# PROC010C_XDS110_Interface_1A.net
KiCad netlist of a schematic drawn in Altium Designer
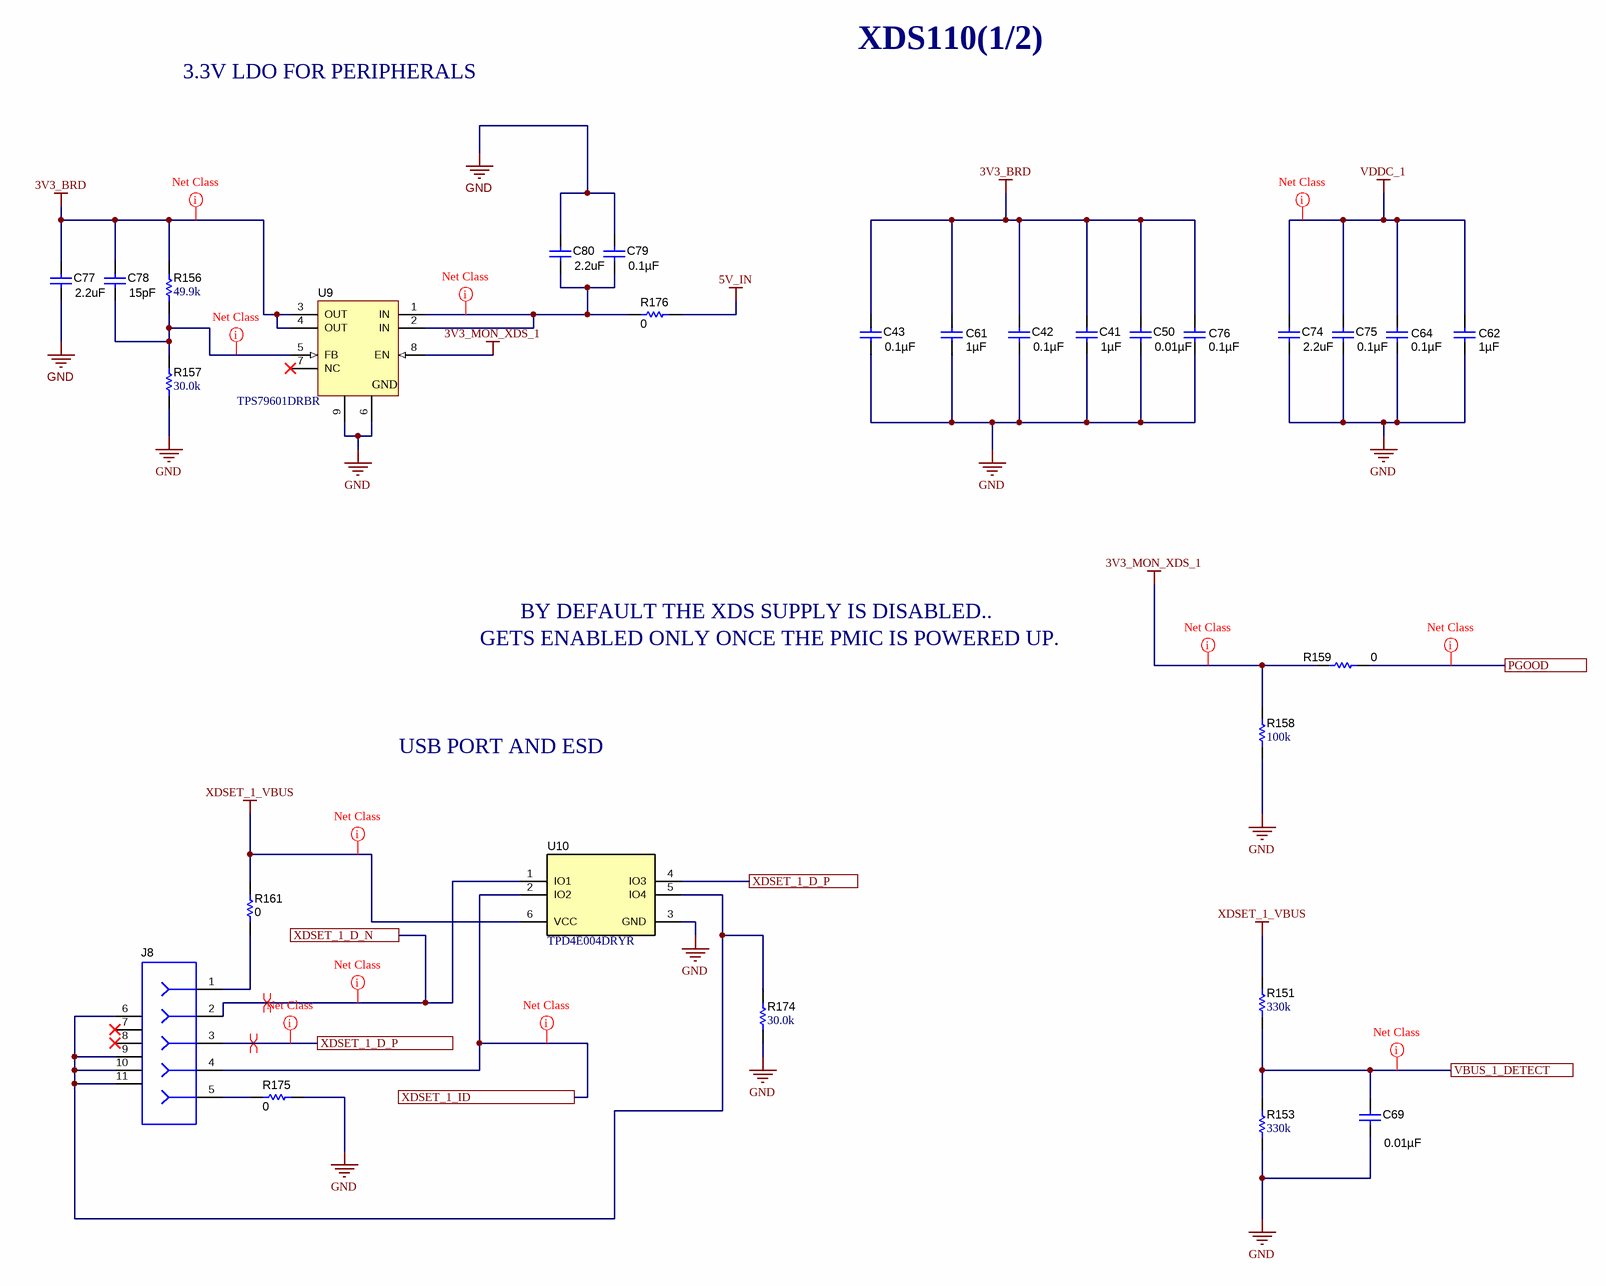
[diagram p0: PROC010C_XDS110 Interface_1A.SchDoc]

(export (version "E")
  (design (tool "Eeschema 10.0.6"))
  (components
    (comp (ref "C41")
      (value "C1005X7S0J105M050BC")
      (footprint "0402L")
      (description "CAP, CERM, 1 µF, 6.3 V,+/- 20%, X7S, 0402")
      (fields (field (name "MANUFACTURER") "TDK") (field (name "VALUEDISPLAYED") "1µF"))
      (libsource (lib "Altium Vault - TI") (part "Capacitor"))
    )
    (comp (ref "C42")
      (value "C0402C104K8RACTU")
      (footprint "0402L")
      (description "CAP, CERM, 0.1 µF, 10 V,+/- 10%, X7R, 0402")
      (fields (field (name "MANUFACTURER") "Kemet") (field (name "VALUEDISPLAYED") "0.1µF"))
      (libsource (lib "Altium Vault - TI") (part "Capacitor"))
    )
    (comp (ref "C43")
      (value "C0402C104K8RACTU")
      (footprint "0402L")
      (description "CAP, CERM, 0.1 µF, 10 V,+/- 10%, X7R, 0402")
      (fields (field (name "MANUFACTURER") "Kemet") (field (name "VALUEDISPLAYED") "0.1µF"))
      (libsource (lib "Altium Vault - TI") (part "Capacitor"))
    )
    (comp (ref "C50")
      (value "C1005X7R1E103K050BB")
      (footprint "0402L")
      (description "CAP, CERM, 0.01 µF, 25 V,+/- 10%, X7R, 0402")
      (fields (field (name "MANUFACTURER") "TDK") (field (name "VALUEDISPLAYED") "0.01µF"))
      (libsource (lib "Altium Vault - TI") (part "Capacitor"))
    )
    (comp (ref "C61")
      (value "C1005X7S0J105M050BC")
      (footprint "0402L")
      (description "CAP, CERM, 1 µF, 6.3 V,+/- 20%, X7S, 0402")
      (fields (field (name "MANUFACTURER") "TDK") (field (name "VALUEDISPLAYED") "1µF"))
      (libsource (lib "Altium Vault - TI") (part "Capacitor"))
    )
    (comp (ref "C62")
      (value "C1005X7S0J105M050BC")
      (footprint "0402L")
      (description "CAP, CERM, 1 µF, 6.3 V,+/- 20%, X7S, 0402")
      (fields (field (name "MANUFACTURER") "TDK") (field (name "VALUEDISPLAYED") "1µF"))
      (libsource (lib "Altium Vault - TI") (part "Capacitor"))
    )
    (comp (ref "C64")
      (value "C0402C104K8RACTU")
      (footprint "0402L")
      (description "CAP, CERM, 0.1 µF, 10 V,+/- 10%, X7R, 0402")
      (fields (field (name "MANUFACTURER") "Kemet") (field (name "VALUEDISPLAYED") "0.1µF"))
      (libsource (lib "Altium Vault - TI") (part "Capacitor"))
    )
    (comp (ref "C69")
      (value "C0402C103K4RACTU")
      (footprint "0402L")
      (description "CAP, CERM, 0.01 µF, 16 V,+/- 10%, X7R, 0402")
      (fields (field (name "MANUFACTURER") "Kemet") (field (name "VALUEDISPLAYED") "0.01µF"))
      (libsource (lib "Altium Vault - TI") (part "Capacitor"))
    )
    (comp (ref "C74")
      (value "C1005X7S1A225K050BC")
      (footprint "0402_065L")
      (description "CAP, CERM, 2.2 uF, 10 V, +/- 10%, X7S, 0402")
      (fields
        (field (name "MANUFACTURER") "TDK")
        (field (name "VALUEDISPLAYED") "2.2uF")
        (field (name "PUBLISHER") "Texas Instruments")
      )
      (libsource (lib "Altium Vault - TI") (part "CMP-0006302-2"))
    )
    (comp (ref "C75")
      (value "C0402C104K8RACTU")
      (footprint "0402L")
      (description "CAP, CERM, 0.1 µF, 10 V,+/- 10%, X7R, 0402")
      (fields (field (name "MANUFACTURER") "Kemet") (field (name "VALUEDISPLAYED") "0.1µF"))
      (libsource (lib "Altium Vault - TI") (part "Capacitor"))
    )
    (comp (ref "C76")
      (value "C0402C104K8RACTU")
      (footprint "0402L")
      (description "CAP, CERM, 0.1 µF, 10 V,+/- 10%, X7R, 0402")
      (fields (field (name "MANUFACTURER") "Kemet") (field (name "VALUEDISPLAYED") "0.1µF"))
      (libsource (lib "Altium Vault - TI") (part "Capacitor"))
    )
    (comp (ref "C77")
      (value "C1005X7S1A225K050BC")
      (footprint "0402_065L")
      (description "CAP, CERM, 2.2 uF, 10 V, +/- 10%, X7S, 0402")
      (fields
        (field (name "MANUFACTURER") "TDK")
        (field (name "VALUEDISPLAYED") "2.2uF")
        (field (name "PUBLISHER") "Texas Instruments")
      )
      (libsource (lib "Altium Vault - TI") (part "CMP-0006302-2"))
    )
    (comp (ref "C78")
      (value "04025A150FAT2A")
      (footprint "0402L")
      (description "CAP, CERM, 15 pF, 50 V,+/- 1%, C0G/NP0, 0402")
      (fields (field (name "MANUFACTURER") "AVX") (field (name "VALUEDISPLAYED") "15pF"))
      (libsource (lib "Altium Vault - TI") (part "Capacitor"))
    )
    (comp (ref "C79")
      (value "C0402C104K8RACTU")
      (footprint "0402L")
      (description "CAP, CERM, 0.1 µF, 10 V,+/- 10%, X7R, 0402")
      (fields (field (name "MANUFACTURER") "Kemet") (field (name "VALUEDISPLAYED") "0.1µF"))
      (libsource (lib "Altium Vault - TI") (part "Capacitor"))
    )
    (comp (ref "C80")
      (value "C1005X7S1A225K050BC")
      (footprint "0402_065L")
      (description "CAP, CERM, 2.2 uF, 10 V, +/- 10%, X7S, 0402")
      (fields
        (field (name "MANUFACTURER") "TDK")
        (field (name "VALUEDISPLAYED") "2.2uF")
        (field (name "PUBLISHER") "Texas Instruments")
      )
      (libsource (lib "Altium Vault - TI") (part "CMP-0006302-2"))
    )
    (comp (ref "J8")
      (value "105017-0001")
      (footprint "CONN_105017-0001")
      (description "Connector, Receptacle, Micro-USB Type B, R/A, Bottom Mount SMT")
      (fields (field (name "MANUFACTURER") "Molex") (field (name "PUBLISHER") "Texas Instruments"))
      (libsource (lib "Altium Vault - TI") (part "CONN_105017-0001"))
    )
    (comp (ref "R151")
      (value "CRCW0402330KFKED")
      (footprint "0402L")
      (description "RES, 330 k, 1%, 0.063 W, AEC-Q200 Grade 0, 0402")
      (fields (field (name "MANUFACTURER") "Vishay-Dale") (field (name "VALUEDISPLAYED") "330k"))
      (libsource (lib "Altium Vault - TI") (part "Resistor"))
    )
    (comp (ref "R153")
      (value "CRCW0402330KFKED")
      (footprint "0402L")
      (description "RES, 330 k, 1%, 0.063 W, AEC-Q200 Grade 0, 0402")
      (fields (field (name "MANUFACTURER") "Vishay-Dale") (field (name "VALUEDISPLAYED") "330k"))
      (libsource (lib "Altium Vault - TI") (part "Resistor"))
    )
    (comp (ref "R156")
      (value "CRCW040249K9FKED")
      (footprint "0402L")
      (description "RES, 49.9 k, 1%, 0.063 W, AEC-Q200 Grade 0, 0402")
      (fields (field (name "MANUFACTURER") "Vishay-Dale") (field (name "VALUEDISPLAYED") "49.9k"))
      (libsource (lib "Altium Vault - TI") (part "Resistor"))
    )
    (comp (ref "R157")
      (value "CRCW040230K0FKED")
      (footprint "0402L")
      (description "RES, 30.0 k, 1%, 0.063 W, AEC-Q200 Grade 0, 0402")
      (fields (field (name "MANUFACTURER") "Vishay-Dale") (field (name "VALUEDISPLAYED") "30.0k"))
      (libsource (lib "Altium Vault - TI") (part "Resistor"))
    )
    (comp (ref "R158")
      (value "CRCW0402100KFKED")
      (footprint "0402L")
      (description "RES, 100 k, 1%, 0.063 W, AEC-Q200 Grade 0, 0402")
      (fields (field (name "MANUFACTURER") "Vishay-Dale") (field (name "VALUEDISPLAYED") "100k"))
      (libsource (lib "Altium Vault - TI") (part "Resistor"))
    )
    (comp (ref "R159")
      (value "ERJ-2GE0R00X")
      (footprint "0402L")
      (description "RES, 0, 5%, 0.063 W, 0402")
      (fields
        (field (name "MANUFACTURER") "Panasonic")
        (field (name "VALUEDISPLAYED") "0")
        (field (name "PUBLISHER") "Texas Instruments")
      )
      (libsource (lib "Altium Vault - TI") (part "Resistor"))
    )
    (comp (ref "R161")
      (value "MCT06030Z0000ZP500")
      (footprint "0603")
      (description "RES, 0, 5%, 0.125 W, 0603")
      (fields
        (field (name "MANUFACTURER") "Vishay/Beyschlag")
        (field (name "VALUEDISPLAYED") "0")
        (field (name "PUBLISHER") "Texas Instruments")
      )
      (libsource (lib "Altium Vault - TI") (part "Resistor"))
    )
    (comp (ref "R174")
      (value "CRCW040230K0FKED")
      (footprint "0402L")
      (description "RES, 30.0 k, 1%, 0.063 W, AEC-Q200 Grade 0, 0402")
      (fields (field (name "MANUFACTURER") "Vishay-Dale") (field (name "VALUEDISPLAYED") "30.0k"))
      (libsource (lib "Altium Vault - TI") (part "Resistor"))
    )
    (comp (ref "R175")
      (value "MCT06030Z0000ZP500")
      (footprint "0603")
      (description "RES, 0, 5%, 0.125 W, 0603")
      (fields
        (field (name "MANUFACTURER") "Vishay/Beyschlag")
        (field (name "VALUEDISPLAYED") "0")
        (field (name "PUBLISHER") "Texas Instruments")
      )
      (libsource (lib "Altium Vault - TI") (part "Resistor"))
    )
    (comp (ref "R176")
      (value "MCT06030Z0000ZP500")
      (footprint "0603")
      (description "RES, 0, 5%, 0.125 W, 0603")
      (fields
        (field (name "MANUFACTURER") "Vishay/Beyschlag")
        (field (name "VALUEDISPLAYED") "0")
        (field (name "PUBLISHER") "Texas Instruments")
      )
      (libsource (lib "Altium Vault - TI") (part "Resistor"))
    )
    (comp (ref "U9")
      (value "TPS79601DRBR")
      (footprint "DRB0008B")
      (fields (field (name "MANUFACTURER") "Texas Instruments") (field (name "PARTNUMBER") "TPS79601DRBR"))
      (libsource (lib "Altium Vault - TI") (part "CMP-0036402-3"))
    )
    (comp (ref "U10")
      (value "TPD4E004DRYR")
      (footprint "DRY0006A")
      (fields (field (name "MANUFACTURER") "Texas Instruments") (field (name "PARTNUMBER") "TPD4E004DRYR"))
      (libsource (lib "Altium Vault - TI") (part "CMP-0043115-2"))
    )
  )
  (nets
    (net (code "1") (name "/PGOOD") (class "Default")
      (node (ref "R159") (pin "1") (pinfunction "1_1") (pintype "passive"))
    )
    (net (code "2") (name "/VBUS_1_DETECT") (class "Default")
      (node (ref "C69") (pin "2") (pinfunction "2_2") (pintype "passive"))
      (node (ref "R151") (pin "1") (pinfunction "1_1") (pintype "passive"))
      (node (ref "R153") (pin "2") (pinfunction "2_2") (pintype "passive"))
    )
    (net (code "3") (name "/XDSET_1_D_N") (class "Default")
      (node (ref "J8") (pin "2") (pintype "passive"))
      (node (ref "U10") (pin "1") (pinfunction "IO1_1") (pintype "passive"))
    )
    (net (code "4") (name "/XDSET_1_D_P") (class "Default")
      (node (ref "J8") (pin "3") (pintype "passive"))
      (node (ref "U10") (pin "4") (pinfunction "IO3_4") (pintype "passive"))
    )
    (net (code "5") (name "/XDSET_1_ID") (class "Default")
      (node (ref "J8") (pin "4") (pintype "passive"))
      (node (ref "U10") (pin "2") (pinfunction "IO2_2") (pintype "passive"))
    )
    (net (code "6") (name "3V3_BRD") (class "Default")
      (node (ref "C41") (pin "2") (pinfunction "2_2") (pintype "passive"))
      (node (ref "C42") (pin "2") (pinfunction "2_2") (pintype "passive"))
      (node (ref "C43") (pin "2") (pinfunction "2_2") (pintype "passive"))
      (node (ref "C50") (pin "2") (pinfunction "2_2") (pintype "passive"))
      (node (ref "C61") (pin "2") (pinfunction "2_2") (pintype "passive"))
      (node (ref "C76") (pin "2") (pinfunction "2_2") (pintype "passive"))
      (node (ref "C77") (pin "2") (pinfunction "2_2") (pintype "passive"))
      (node (ref "C78") (pin "2") (pinfunction "2_2") (pintype "passive"))
      (node (ref "R156") (pin "2") (pinfunction "2_2") (pintype "passive"))
      (node (ref "U9") (pin "3") (pinfunction "OUT_3") (pintype "power_in"))
      (node (ref "U9") (pin "4") (pinfunction "OUT_4") (pintype "power_in"))
    )
    (net (code "7") (name "3V3_MON_XDS_1") (class "Default")
      (node (ref "R158") (pin "2") (pinfunction "2_2") (pintype "passive"))
      (node (ref "R159") (pin "2") (pinfunction "2_2") (pintype "passive"))
      (node (ref "U9") (pin "8") (pinfunction "EN_8") (pintype "input"))
    )
    (net (code "8") (name "5V_IN") (class "Default")
      (node (ref "R176") (pin "2") (pinfunction "2_2") (pintype "passive"))
    )
    (net (code "9") (name "GND") (class "Default")
      (node (ref "C41") (pin "1") (pinfunction "1_1") (pintype "passive"))
      (node (ref "C42") (pin "1") (pinfunction "1_1") (pintype "passive"))
      (node (ref "C43") (pin "1") (pinfunction "1_1") (pintype "passive"))
      (node (ref "C50") (pin "1") (pinfunction "1_1") (pintype "passive"))
      (node (ref "C61") (pin "1") (pinfunction "1_1") (pintype "passive"))
      (node (ref "C62") (pin "1") (pinfunction "1_1") (pintype "passive"))
      (node (ref "C64") (pin "1") (pinfunction "1_1") (pintype "passive"))
      (node (ref "C69") (pin "1") (pinfunction "1_1") (pintype "passive"))
      (node (ref "C74") (pin "1") (pinfunction "1_1") (pintype "passive"))
      (node (ref "C75") (pin "1") (pinfunction "1_1") (pintype "passive"))
      (node (ref "C76") (pin "1") (pinfunction "1_1") (pintype "passive"))
      (node (ref "C77") (pin "1") (pinfunction "1_1") (pintype "passive"))
      (node (ref "C79") (pin "1") (pinfunction "1_1") (pintype "passive"))
      (node (ref "C80") (pin "1") (pinfunction "1_1") (pintype "passive"))
      (node (ref "R153") (pin "1") (pinfunction "1_1") (pintype "passive"))
      (node (ref "R157") (pin "1") (pinfunction "1_1") (pintype "passive"))
      (node (ref "R158") (pin "1") (pinfunction "1_1") (pintype "passive"))
      (node (ref "R174") (pin "1") (pinfunction "1_1") (pintype "passive"))
      (node (ref "R175") (pin "1") (pinfunction "1_1") (pintype "passive"))
      (node (ref "U10") (pin "3") (pinfunction "GND_3") (pintype "power_in"))
      (node (ref "U9") (pin "6") (pinfunction "GND_6") (pintype "power_in"))
      (node (ref "U9") (pin "9") (pinfunction "GND_9") (pintype "power_in"))
    )
    (net (code "10") (name "Net-(C79-Pad2)") (class "Default")
      (node (ref "C79") (pin "2") (pinfunction "2_2") (pintype "passive"))
      (node (ref "C80") (pin "2") (pinfunction "2_2") (pintype "passive"))
      (node (ref "R176") (pin "1") (pinfunction "1_1") (pintype "passive"))
      (node (ref "U9") (pin "1") (pinfunction "IN_1") (pintype "power_in"))
      (node (ref "U9") (pin "2") (pinfunction "IN_2") (pintype "power_in"))
    )
    (net (code "11") (name "Net-(J8-Pad1)") (class "Default")
      (node (ref "J8") (pin "1") (pintype "passive"))
      (node (ref "R161") (pin "1") (pinfunction "1_1") (pintype "passive"))
    )
    (net (code "12") (name "Net-(J8-Pad5)") (class "Default")
      (node (ref "J8") (pin "5") (pintype "passive"))
      (node (ref "R175") (pin "2") (pinfunction "2_2") (pintype "passive"))
    )
    (net (code "13") (name "Net-(U9-FB)") (class "Default")
      (node (ref "C78") (pin "1") (pinfunction "1_1") (pintype "passive"))
      (node (ref "R156") (pin "1") (pinfunction "1_1") (pintype "passive"))
      (node (ref "R157") (pin "2") (pinfunction "2_2") (pintype "passive"))
      (node (ref "U9") (pin "5") (pinfunction "FB_5") (pintype "input"))
    )
    (net (code "14") (name "Net-(U10-IO4)") (class "Default")
      (node (ref "J8") (pin "10") (pintype "passive"))
      (node (ref "J8") (pin "11") (pintype "passive"))
      (node (ref "J8") (pin "6") (pintype "passive"))
      (node (ref "J8") (pin "9") (pintype "passive"))
      (node (ref "R174") (pin "2") (pinfunction "2_2") (pintype "passive"))
      (node (ref "U10") (pin "5") (pinfunction "IO4_5") (pintype "passive"))
    )
    (net (code "15") (name "VDDC_1") (class "Default")
      (node (ref "C62") (pin "2") (pinfunction "2_2") (pintype "passive"))
      (node (ref "C64") (pin "2") (pinfunction "2_2") (pintype "passive"))
      (node (ref "C74") (pin "2") (pinfunction "2_2") (pintype "passive"))
      (node (ref "C75") (pin "2") (pinfunction "2_2") (pintype "passive"))
    )
    (net (code "16") (name "XDSET_1_VBUS") (class "Default")
      (node (ref "R151") (pin "2") (pinfunction "2_2") (pintype "passive"))
      (node (ref "R161") (pin "2") (pinfunction "2_2") (pintype "passive"))
      (node (ref "U10") (pin "6") (pinfunction "VCC_6") (pintype "power_in"))
    )
    (net (code "17") (name "unconnected-(J8-Pad7)") (class "Default")
      (node (ref "J8") (pin "7") (pintype "passive+no_connect"))
    )
    (net (code "18") (name "unconnected-(J8-Pad8)") (class "Default")
      (node (ref "J8") (pin "8") (pintype "passive+no_connect"))
    )
    (net (code "19") (name "unconnected-(U9-NC-Pad7)") (class "Default")
      (node (ref "U9") (pin "7") (pinfunction "NC_7") (pintype "passive+no_connect"))
    )
  )
)
